# custom_components.net
KiCad netlist of a schematic drawn in EAGLE
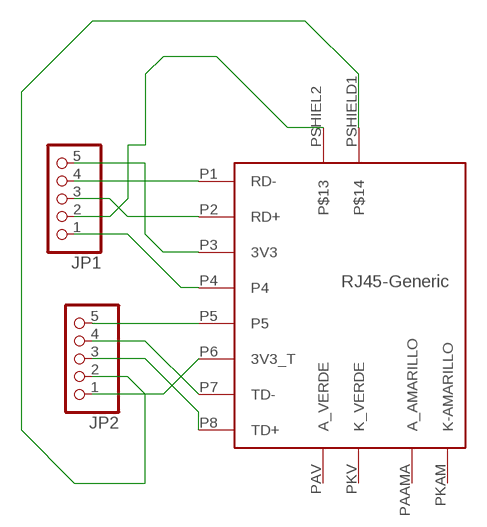
[diagram p0: schematic, sheet 1]

(export (version "E")
  (design (tool "Eeschema 10.0.6"))
  (components
    (comp (ref "JP1")
      (value "PINHD-1X5")
      (footprint "eagle-import:1X05")
      (libsource (lib "eagle-import") (part "PINHD-1X5"))
    )
    (comp (ref "JP2")
      (value "PINHD-1X5")
      (footprint "eagle-import:1X05")
      (libsource (lib "eagle-import") (part "PINHD-1X5"))
    )
    (comp (ref "U$2")
      (value "RJ-45-GENERIC")
      (footprint "eagle-import:RJ45-GENERIC")
      (libsource (lib "eagle-import") (part "RJ-45-GENERIC"))
    )
  )
  (nets
    (net (code "1") (name "Net-(JP1-Pad1)") (class "Default")
      (node (ref "JP1") (pin "1") (pinfunction "1_1") (pintype "passive"))
      (node (ref "U$2") (pin "P4") (pinfunction "P4_P4") (pintype "bidirectional"))
    )
    (net (code "2") (name "Net-(JP2-Pad5)") (class "Default")
      (node (ref "JP2") (pin "5") (pinfunction "5_5") (pintype "passive"))
      (node (ref "U$2") (pin "P5") (pinfunction "P5_P5") (pintype "bidirectional"))
    )
    (net (code "3") (name "Net-(U$2-3V3)") (class "Default")
      (node (ref "JP1") (pin "5") (pinfunction "5_5") (pintype "passive"))
      (node (ref "U$2") (pin "P3") (pinfunction "3V3_P3") (pintype "bidirectional"))
    )
    (net (code "4") (name "Net-(U$2-3V3_T)") (class "Default")
      (node (ref "JP2") (pin "1") (pinfunction "1_1") (pintype "passive"))
      (node (ref "U$2") (pin "P6") (pinfunction "3V3_T_P6") (pintype "bidirectional"))
    )
    (net (code "5") (name "Net-(U$2-P$13)") (class "Default")
      (node (ref "JP1") (pin "2") (pinfunction "2_2") (pintype "passive"))
      (node (ref "U$2") (pin "PSHIEL2") (pinfunction "P$13_PSHIEL2") (pintype "bidirectional"))
    )
    (net (code "6") (name "Net-(U$2-P$14)") (class "Default")
      (node (ref "JP2") (pin "2") (pinfunction "2_2") (pintype "passive"))
      (node (ref "U$2") (pin "PSHIELD1") (pinfunction "P$14_PSHIELD1") (pintype "bidirectional"))
    )
    (net (code "7") (name "Net-(U$2-RD+)") (class "Default")
      (node (ref "JP1") (pin "3") (pinfunction "3_3") (pintype "passive"))
      (node (ref "U$2") (pin "P2") (pinfunction "RD+_P2") (pintype "bidirectional"))
    )
    (net (code "8") (name "Net-(U$2-RD-)") (class "Default")
      (node (ref "JP1") (pin "4") (pinfunction "4_4") (pintype "passive"))
      (node (ref "U$2") (pin "P1") (pinfunction "RD-_P1") (pintype "bidirectional"))
    )
    (net (code "9") (name "Net-(U$2-TD+)") (class "Default")
      (node (ref "JP2") (pin "3") (pinfunction "3_3") (pintype "passive"))
      (node (ref "U$2") (pin "P8") (pinfunction "TD+_P8") (pintype "bidirectional"))
    )
    (net (code "10") (name "Net-(U$2-TD-)") (class "Default")
      (node (ref "JP2") (pin "4") (pinfunction "4_4") (pintype "passive"))
      (node (ref "U$2") (pin "P7") (pinfunction "TD-_P7") (pintype "bidirectional"))
    )
    (net (code "11") (name "unconnected-(U$2-A_AMARILLO-PadPAAMA)") (class "Default")
      (node (ref "U$2") (pin "PAAMA") (pinfunction "A_AMARILLO_PAAMA") (pintype "bidirectional"))
    )
    (net (code "12") (name "unconnected-(U$2-A_VERDE-PadPAV)") (class "Default")
      (node (ref "U$2") (pin "PAV") (pinfunction "A_VERDE_PAV") (pintype "bidirectional"))
    )
    (net (code "13") (name "unconnected-(U$2-K-AMARILLO-PadPKAM)") (class "Default")
      (node (ref "U$2") (pin "PKAM") (pinfunction "K-AMARILLO_PKAM") (pintype "bidirectional"))
    )
    (net (code "14") (name "unconnected-(U$2-K_VERDE-PadPKV)") (class "Default")
      (node (ref "U$2") (pin "PKV") (pinfunction "K_VERDE_PKV") (pintype "bidirectional"))
    )
  )
)
